# Temp_Bank.net
KiCad netlist of a schematic drawn in Altium Designer
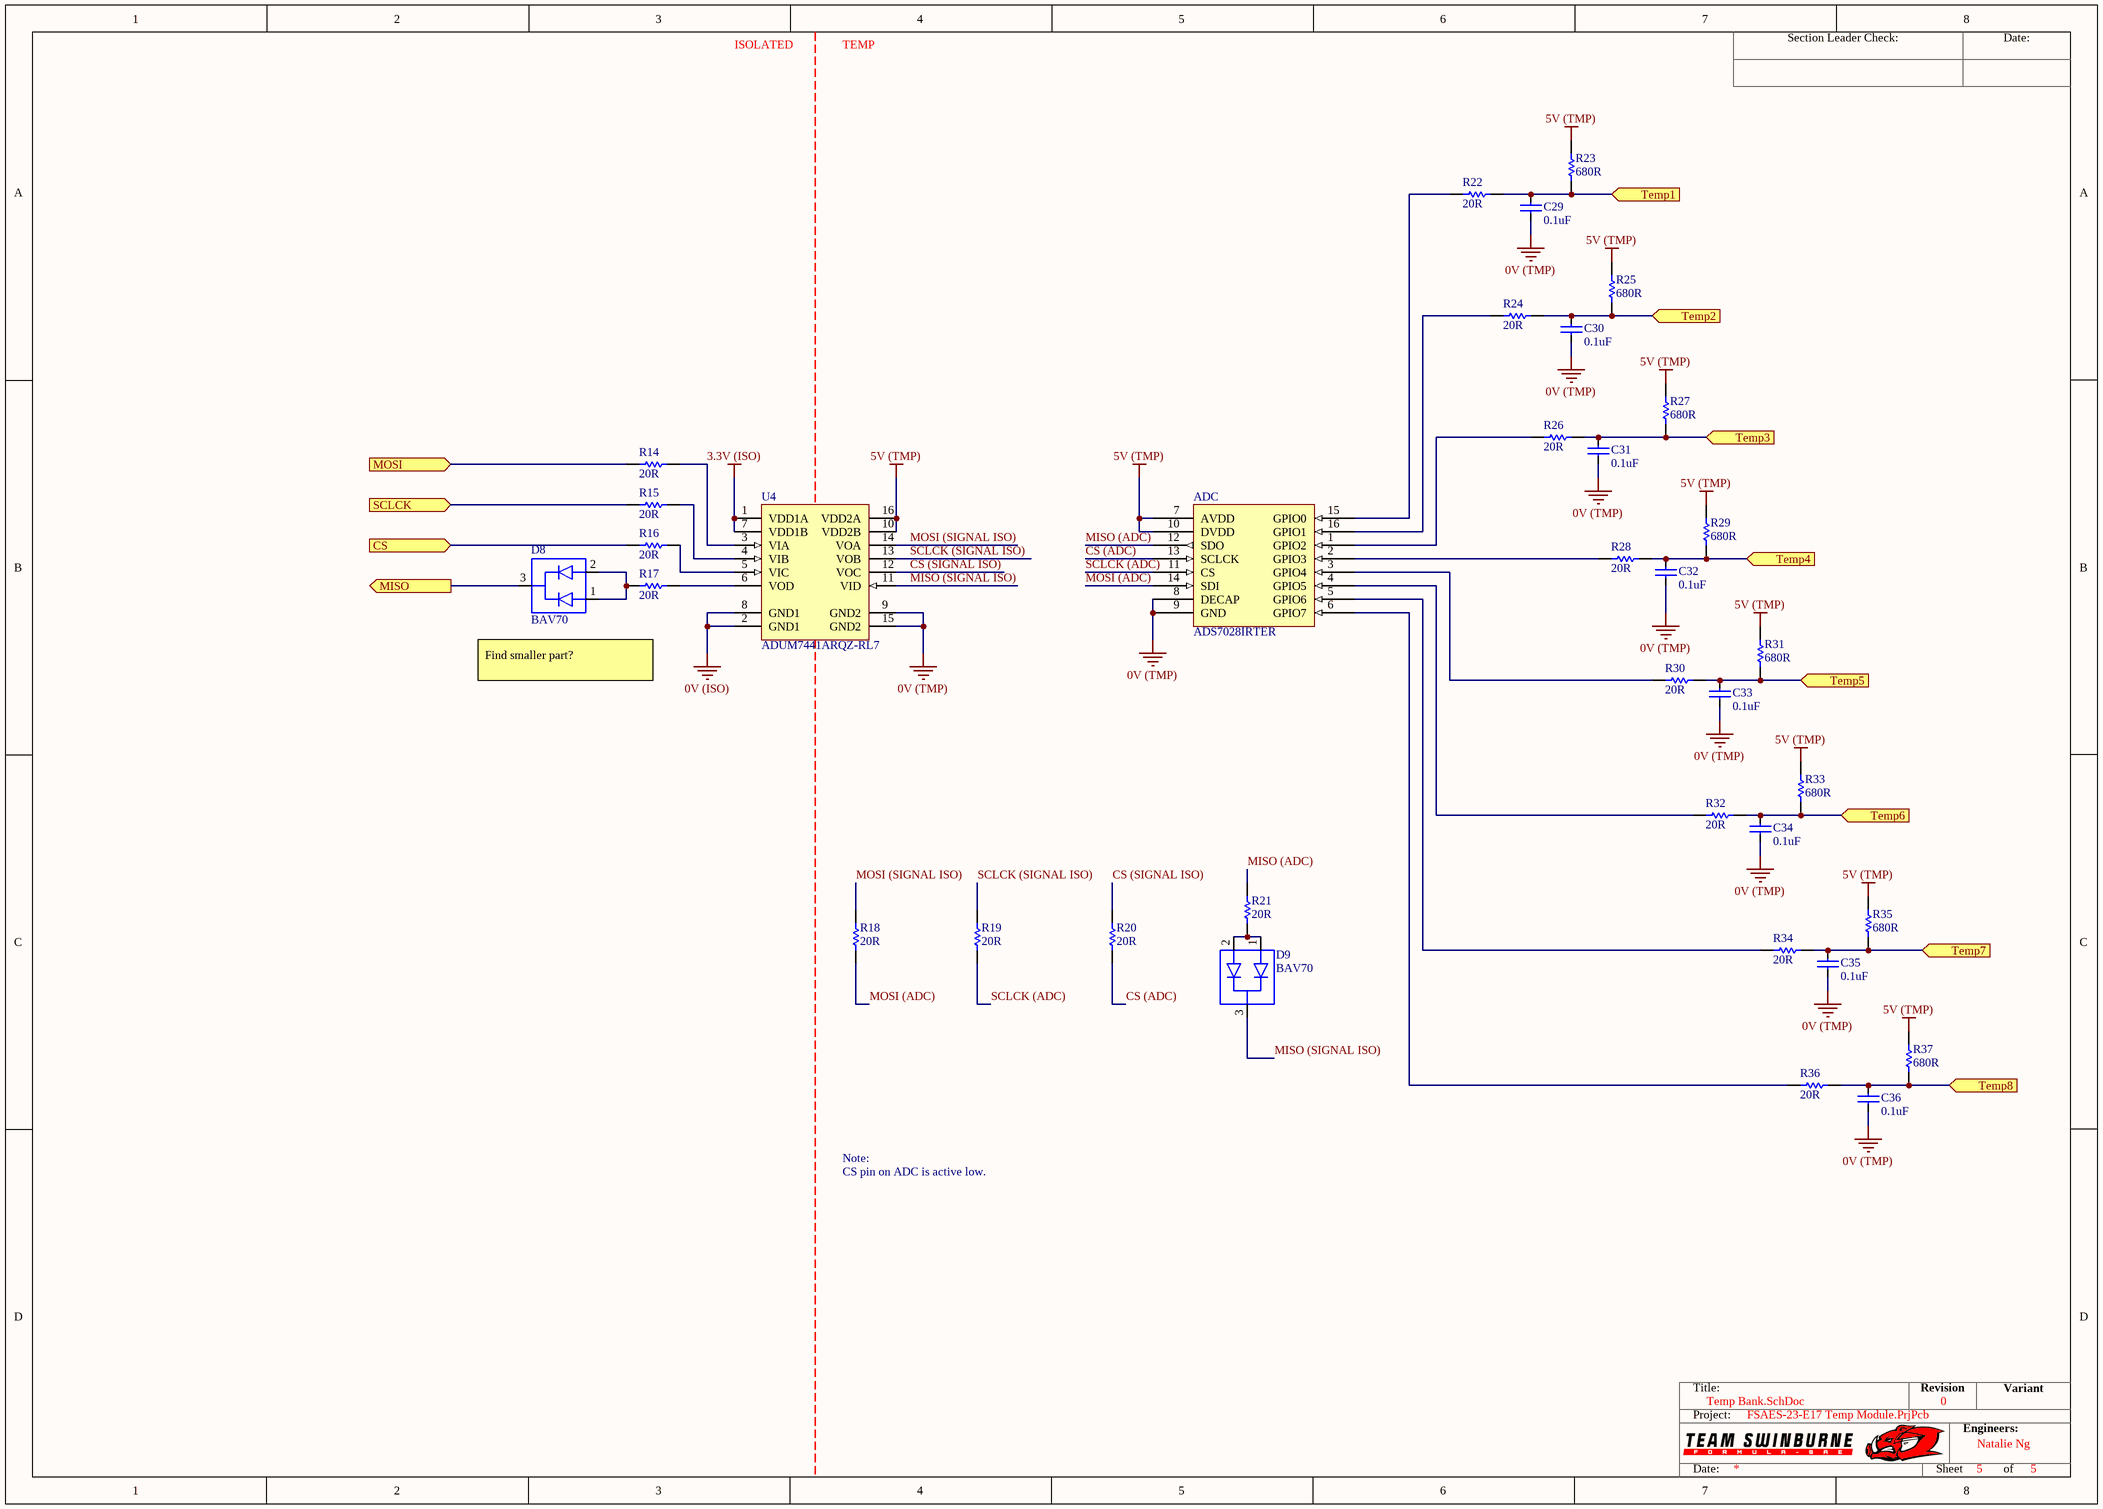
[diagram p0: Temp Bank.SchDoc]

(export (version "E")
  (design (tool "Eeschema 10.0.6"))
  (components
    (comp (ref "ADC")
      (value "ADS7028IRTER")
      (footprint "QFN50P300X300X80_HS-17N")
      (description "Small 8-channel 12-bit analog-to-digital converter (ADC) with SPI, GPIOs and CRC 16-WQFN -40 to 85")
      (libsource (lib "Team Swinburne") (part "ADS7028IRTER-Symbol-1"))
    )
    (comp (ref "C29")
      (value "0.1uF")
      (footprint "0805")
      (description "Cap Ceramic 0.1uF 25V X7R 10% Pad SMD 0805 125C Automotive T/R")
      (fields (field (name "TOLERANCE") "10%"))
      (libsource (lib "Team Swinburne") (part "Capacitors"))
    )
    (comp (ref "C30")
      (value "0.1uF")
      (footprint "0805")
      (description "Cap Ceramic 0.1uF 25V X7R 10% Pad SMD 0805 125C Automotive T/R")
      (fields (field (name "TOLERANCE") "10%"))
      (libsource (lib "Team Swinburne") (part "Capacitors"))
    )
    (comp (ref "C31")
      (value "0.1uF")
      (footprint "0805")
      (description "Cap Ceramic 0.1uF 25V X7R 10% Pad SMD 0805 125C Automotive T/R")
      (fields (field (name "TOLERANCE") "10%"))
      (libsource (lib "Team Swinburne") (part "Capacitors"))
    )
    (comp (ref "C32")
      (value "0.1uF")
      (footprint "0805")
      (description "Cap Ceramic 0.1uF 25V X7R 10% Pad SMD 0805 125C Automotive T/R")
      (fields (field (name "TOLERANCE") "10%"))
      (libsource (lib "Team Swinburne") (part "Capacitors"))
    )
    (comp (ref "C33")
      (value "0.1uF")
      (footprint "0805")
      (description "Cap Ceramic 0.1uF 25V X7R 10% Pad SMD 0805 125C Automotive T/R")
      (fields (field (name "TOLERANCE") "10%"))
      (libsource (lib "Team Swinburne") (part "Capacitors"))
    )
    (comp (ref "C34")
      (value "0.1uF")
      (footprint "0805")
      (description "Cap Ceramic 0.1uF 25V X7R 10% Pad SMD 0805 125C Automotive T/R")
      (fields (field (name "TOLERANCE") "10%"))
      (libsource (lib "Team Swinburne") (part "Capacitors"))
    )
    (comp (ref "C35")
      (value "0.1uF")
      (footprint "0805")
      (description "Cap Ceramic 0.1uF 25V X7R 10% Pad SMD 0805 125C Automotive T/R")
      (fields (field (name "TOLERANCE") "10%"))
      (libsource (lib "Team Swinburne") (part "Capacitors"))
    )
    (comp (ref "C36")
      (value "0.1uF")
      (footprint "0805")
      (description "Cap Ceramic 0.1uF 25V X7R 10% Pad SMD 0805 125C Automotive T/R")
      (fields (field (name "TOLERANCE") "10%"))
      (libsource (lib "Team Swinburne") (part "Capacitors"))
    )
    (comp (ref "D8")
      (value "BAV70")
      (footprint "BAV70-Footprint-1")
      (description "DIODE ARRAY GP 70V 200mA SOT23-3")
      (libsource (lib "Team Swinburne") (part "BAV70-Symbol-1"))
    )
    (comp (ref "D9")
      (value "BAV70")
      (footprint "BAV70-Footprint-1")
      (description "DIODE ARRAY GP 70V 200mA SOT23-3")
      (libsource (lib "Team Swinburne") (part "BAV70-Symbol-1"))
    )
    (comp (ref "R14")
      (value "20R")
      (footprint "RESC0603")
      (description "RES SMD 20 OHM JUMPER 1/10W 0603")
      (fields (field (name "TOLERANCE") "1%"))
      (libsource (lib "Team Swinburne") (part "Resistor"))
    )
    (comp (ref "R15")
      (value "20R")
      (footprint "RESC0603")
      (description "RES SMD 20 OHM JUMPER 1/10W 0603")
      (fields (field (name "TOLERANCE") "1%"))
      (libsource (lib "Team Swinburne") (part "Resistor"))
    )
    (comp (ref "R16")
      (value "20R")
      (footprint "RESC0603")
      (description "RES SMD 20 OHM JUMPER 1/10W 0603")
      (fields (field (name "TOLERANCE") "1%"))
      (libsource (lib "Team Swinburne") (part "Resistor"))
    )
    (comp (ref "R17")
      (value "20R")
      (footprint "RESC0603")
      (description "RES SMD 20 OHM JUMPER 1/10W 0603")
      (fields (field (name "TOLERANCE") "1%"))
      (libsource (lib "Team Swinburne") (part "Resistor"))
    )
    (comp (ref "R18")
      (value "20R")
      (footprint "RESC0603")
      (description "RES SMD 20 OHM JUMPER 1/10W 0603")
      (fields (field (name "TOLERANCE") "1%"))
      (libsource (lib "Team Swinburne") (part "Resistor"))
    )
    (comp (ref "R19")
      (value "20R")
      (footprint "RESC0603")
      (description "RES SMD 20 OHM JUMPER 1/10W 0603")
      (fields (field (name "TOLERANCE") "1%"))
      (libsource (lib "Team Swinburne") (part "Resistor"))
    )
    (comp (ref "R20")
      (value "20R")
      (footprint "RESC0603")
      (description "RES SMD 20 OHM JUMPER 1/10W 0603")
      (fields (field (name "TOLERANCE") "1%"))
      (libsource (lib "Team Swinburne") (part "Resistor"))
    )
    (comp (ref "R21")
      (value "20R")
      (footprint "RESC0603")
      (description "RES SMD 20 OHM JUMPER 1/10W 0603")
      (fields (field (name "TOLERANCE") "1%"))
      (libsource (lib "Team Swinburne") (part "Resistor"))
    )
    (comp (ref "R22")
      (value "20R")
      (footprint "RESC0603")
      (description "RES SMD 20 OHM JUMPER 1/10W 0603")
      (fields (field (name "TOLERANCE") "1%"))
      (libsource (lib "Team Swinburne") (part "Resistor"))
    )
    (comp (ref "R23")
      (value "680R")
      (footprint "0805")
      (description "RC0805FR07680RL")
      (fields (field (name "DIGIKEY PART NUMBER") "311-680CRCT-ND") (field (name "TOLERANCE") "0.01"))
      (libsource (lib "Team Swinburne") (part "Resistor"))
    )
    (comp (ref "R24")
      (value "20R")
      (footprint "RESC0603")
      (description "RES SMD 20 OHM JUMPER 1/10W 0603")
      (fields (field (name "TOLERANCE") "1%"))
      (libsource (lib "Team Swinburne") (part "Resistor"))
    )
    (comp (ref "R25")
      (value "680R")
      (footprint "0805")
      (description "RC0805FR07680RL")
      (fields (field (name "DIGIKEY PART NUMBER") "311-680CRCT-ND") (field (name "TOLERANCE") "0.01"))
      (libsource (lib "Team Swinburne") (part "Resistor"))
    )
    (comp (ref "R26")
      (value "20R")
      (footprint "RESC0603")
      (description "RES SMD 20 OHM JUMPER 1/10W 0603")
      (fields (field (name "TOLERANCE") "1%"))
      (libsource (lib "Team Swinburne") (part "Resistor"))
    )
    (comp (ref "R27")
      (value "680R")
      (footprint "0805")
      (description "RC0805FR07680RL")
      (fields (field (name "DIGIKEY PART NUMBER") "311-680CRCT-ND") (field (name "TOLERANCE") "0.01"))
      (libsource (lib "Team Swinburne") (part "Resistor"))
    )
    (comp (ref "R28")
      (value "20R")
      (footprint "RESC0603")
      (description "RES SMD 20 OHM JUMPER 1/10W 0603")
      (fields (field (name "TOLERANCE") "1%"))
      (libsource (lib "Team Swinburne") (part "Resistor"))
    )
    (comp (ref "R29")
      (value "680R")
      (footprint "0805")
      (description "RC0805FR07680RL")
      (fields (field (name "DIGIKEY PART NUMBER") "311-680CRCT-ND") (field (name "TOLERANCE") "0.01"))
      (libsource (lib "Team Swinburne") (part "Resistor"))
    )
    (comp (ref "R30")
      (value "20R")
      (footprint "RESC0603")
      (description "RES SMD 20 OHM JUMPER 1/10W 0603")
      (fields (field (name "TOLERANCE") "1%"))
      (libsource (lib "Team Swinburne") (part "Resistor"))
    )
    (comp (ref "R31")
      (value "680R")
      (footprint "0805")
      (description "RC0805FR07680RL")
      (fields (field (name "DIGIKEY PART NUMBER") "311-680CRCT-ND") (field (name "TOLERANCE") "0.01"))
      (libsource (lib "Team Swinburne") (part "Resistor"))
    )
    (comp (ref "R32")
      (value "20R")
      (footprint "RESC0603")
      (description "RES SMD 20 OHM JUMPER 1/10W 0603")
      (fields (field (name "TOLERANCE") "1%"))
      (libsource (lib "Team Swinburne") (part "Resistor"))
    )
    (comp (ref "R33")
      (value "680R")
      (footprint "0805")
      (description "RC0805FR07680RL")
      (fields (field (name "DIGIKEY PART NUMBER") "311-680CRCT-ND") (field (name "TOLERANCE") "0.01"))
      (libsource (lib "Team Swinburne") (part "Resistor"))
    )
    (comp (ref "R34")
      (value "20R")
      (footprint "RESC0603")
      (description "RES SMD 20 OHM JUMPER 1/10W 0603")
      (fields (field (name "TOLERANCE") "1%"))
      (libsource (lib "Team Swinburne") (part "Resistor"))
    )
    (comp (ref "R35")
      (value "680R")
      (footprint "0805")
      (description "RC0805FR07680RL")
      (fields (field (name "DIGIKEY PART NUMBER") "311-680CRCT-ND") (field (name "TOLERANCE") "0.01"))
      (libsource (lib "Team Swinburne") (part "Resistor"))
    )
    (comp (ref "R36")
      (value "20R")
      (footprint "RESC0603")
      (description "RES SMD 20 OHM JUMPER 1/10W 0603")
      (fields (field (name "TOLERANCE") "1%"))
      (libsource (lib "Team Swinburne") (part "Resistor"))
    )
    (comp (ref "R37")
      (value "680R")
      (footprint "0805")
      (description "RC0805FR07680RL")
      (fields (field (name "DIGIKEY PART NUMBER") "311-680CRCT-ND") (field (name "TOLERANCE") "0.01"))
      (libsource (lib "Team Swinburne") (part "Resistor"))
    )
    (comp (ref "U4")
      (value "ADUM7441ARQZ-RL7")
      (footprint "ADI-RQ-16_M")
      (description "Digital Isolator CMOS 4-CH 1Mbps 16-Pin QSOP T/R")
      (libsource (lib "Team Swinburne") (part "ADI-ADUM7441-RQ-16"))
    )
  )
  (nets
    (net (code "1") (name "/CS") (class "Default")
      (node (ref "R16") (pin "1") (pinfunction "1_1") (pintype "passive"))
    )
    (net (code "2") (name "/CS (ADC)") (class "Default")
      (node (ref "ADC") (pin "13") (pinfunction "SCLCK_13") (pintype "input"))
      (node (ref "R20") (pin "1") (pinfunction "1_1") (pintype "passive"))
    )
    (net (code "3") (name "/CS (SIGNAL ISO)") (class "Default")
      (node (ref "R20") (pin "2") (pinfunction "2_2") (pintype "passive"))
      (node (ref "U4") (pin "12") (pinfunction "VOC_12") (pintype "tri_state"))
    )
    (net (code "4") (name "/MISO") (class "Default")
      (node (ref "D8") (pin "3") (pinfunction "CC_3") (pintype "passive"))
    )
    (net (code "5") (name "/MISO (ADC)") (class "Default")
      (node (ref "ADC") (pin "12") (pinfunction "SDO_12") (pintype "output"))
      (node (ref "R21") (pin "2") (pinfunction "2_2") (pintype "passive"))
    )
    (net (code "6") (name "/MISO (SIGNAL ISO)") (class "Default")
      (node (ref "D9") (pin "3") (pinfunction "CC_3") (pintype "passive"))
      (node (ref "U4") (pin "11") (pinfunction "VID_11") (pintype "input"))
    )
    (net (code "7") (name "/MOSI") (class "Default")
      (node (ref "R14") (pin "1") (pinfunction "1_1") (pintype "passive"))
    )
    (net (code "8") (name "/MOSI (ADC)") (class "Default")
      (node (ref "ADC") (pin "14") (pinfunction "SDI_14") (pintype "input"))
      (node (ref "R18") (pin "1") (pinfunction "1_1") (pintype "passive"))
    )
    (net (code "9") (name "/MOSI (SIGNAL ISO)") (class "Default")
      (node (ref "R18") (pin "2") (pinfunction "2_2") (pintype "passive"))
      (node (ref "U4") (pin "14") (pinfunction "VOA_14") (pintype "tri_state"))
    )
    (net (code "10") (name "/SCLCK") (class "Default")
      (node (ref "R15") (pin "1") (pinfunction "1_1") (pintype "passive"))
    )
    (net (code "11") (name "/SCLCK (ADC)") (class "Default")
      (node (ref "ADC") (pin "11") (pinfunction "CS_11") (pintype "input"))
      (node (ref "R19") (pin "1") (pinfunction "1_1") (pintype "passive"))
    )
    (net (code "12") (name "/SCLCK (SIGNAL ISO)") (class "Default")
      (node (ref "R19") (pin "2") (pinfunction "2_2") (pintype "passive"))
      (node (ref "U4") (pin "13") (pinfunction "VOB_13") (pintype "tri_state"))
    )
    (net (code "13") (name "/Temp1") (class "Default")
      (node (ref "C29") (pin "1") (pinfunction "1_1") (pintype "passive"))
      (node (ref "R22") (pin "2") (pinfunction "2_2") (pintype "passive"))
      (node (ref "R23") (pin "1") (pinfunction "1_1") (pintype "passive"))
    )
    (net (code "14") (name "/Temp2") (class "Default")
      (node (ref "C30") (pin "1") (pinfunction "1_1") (pintype "passive"))
      (node (ref "R24") (pin "2") (pinfunction "2_2") (pintype "passive"))
      (node (ref "R25") (pin "1") (pinfunction "1_1") (pintype "passive"))
    )
    (net (code "15") (name "/Temp3") (class "Default")
      (node (ref "C31") (pin "1") (pinfunction "1_1") (pintype "passive"))
      (node (ref "R26") (pin "2") (pinfunction "2_2") (pintype "passive"))
      (node (ref "R27") (pin "1") (pinfunction "1_1") (pintype "passive"))
    )
    (net (code "16") (name "/Temp4") (class "Default")
      (node (ref "C32") (pin "1") (pinfunction "1_1") (pintype "passive"))
      (node (ref "R28") (pin "2") (pinfunction "2_2") (pintype "passive"))
      (node (ref "R29") (pin "1") (pinfunction "1_1") (pintype "passive"))
    )
    (net (code "17") (name "/Temp5") (class "Default")
      (node (ref "C33") (pin "1") (pinfunction "1_1") (pintype "passive"))
      (node (ref "R30") (pin "2") (pinfunction "2_2") (pintype "passive"))
      (node (ref "R31") (pin "1") (pinfunction "1_1") (pintype "passive"))
    )
    (net (code "18") (name "/Temp6") (class "Default")
      (node (ref "C34") (pin "1") (pinfunction "1_1") (pintype "passive"))
      (node (ref "R32") (pin "2") (pinfunction "2_2") (pintype "passive"))
      (node (ref "R33") (pin "1") (pinfunction "1_1") (pintype "passive"))
    )
    (net (code "19") (name "/Temp7") (class "Default")
      (node (ref "C35") (pin "1") (pinfunction "1_1") (pintype "passive"))
      (node (ref "R34") (pin "2") (pinfunction "2_2") (pintype "passive"))
      (node (ref "R35") (pin "1") (pinfunction "1_1") (pintype "passive"))
    )
    (net (code "20") (name "/Temp8") (class "Default")
      (node (ref "C36") (pin "1") (pinfunction "1_1") (pintype "passive"))
      (node (ref "R36") (pin "2") (pinfunction "2_2") (pintype "passive"))
      (node (ref "R37") (pin "1") (pinfunction "1_1") (pintype "passive"))
    )
    (net (code "21") (name "0V (ISO)") (class "Default")
      (node (ref "U4") (pin "2") (pinfunction "GND1_2") (pintype "power_in"))
      (node (ref "U4") (pin "8") (pinfunction "GND1_8") (pintype "power_in"))
    )
    (net (code "22") (name "0V (TMP)") (class "Default")
      (node (ref "ADC") (pin "8") (pinfunction "DECAP_8") (pintype "power_in"))
      (node (ref "ADC") (pin "9") (pinfunction "GND_9") (pintype "power_in"))
      (node (ref "C29") (pin "2") (pinfunction "2_2") (pintype "passive"))
      (node (ref "C30") (pin "2") (pinfunction "2_2") (pintype "passive"))
      (node (ref "C31") (pin "2") (pinfunction "2_2") (pintype "passive"))
      (node (ref "C32") (pin "2") (pinfunction "2_2") (pintype "passive"))
      (node (ref "C33") (pin "2") (pinfunction "2_2") (pintype "passive"))
      (node (ref "C34") (pin "2") (pinfunction "2_2") (pintype "passive"))
      (node (ref "C35") (pin "2") (pinfunction "2_2") (pintype "passive"))
      (node (ref "C36") (pin "2") (pinfunction "2_2") (pintype "passive"))
      (node (ref "U4") (pin "15") (pinfunction "GND2_15") (pintype "power_in"))
      (node (ref "U4") (pin "9") (pinfunction "GND2_9") (pintype "power_in"))
    )
    (net (code "23") (name "3.3V (ISO)") (class "Default")
      (node (ref "U4") (pin "1") (pinfunction "VDD1A_1") (pintype "power_in"))
      (node (ref "U4") (pin "7") (pinfunction "VDD1B_7") (pintype "power_in"))
    )
    (net (code "24") (name "5V (TMP)") (class "Default")
      (node (ref "ADC") (pin "10") (pinfunction "DVDD_10") (pintype "power_in"))
      (node (ref "ADC") (pin "7") (pinfunction "AVDD_7") (pintype "power_in"))
      (node (ref "R23") (pin "2") (pinfunction "2_2") (pintype "passive"))
      (node (ref "R25") (pin "2") (pinfunction "2_2") (pintype "passive"))
      (node (ref "R27") (pin "2") (pinfunction "2_2") (pintype "passive"))
      (node (ref "R29") (pin "2") (pinfunction "2_2") (pintype "passive"))
      (node (ref "R31") (pin "2") (pinfunction "2_2") (pintype "passive"))
      (node (ref "R33") (pin "2") (pinfunction "2_2") (pintype "passive"))
      (node (ref "R35") (pin "2") (pinfunction "2_2") (pintype "passive"))
      (node (ref "R37") (pin "2") (pinfunction "2_2") (pintype "passive"))
      (node (ref "U4") (pin "10") (pinfunction "VDD2B_10") (pintype "power_in"))
      (node (ref "U4") (pin "16") (pinfunction "VDD2A_16") (pintype "power_in"))
    )
    (net (code "25") (name "Net-(ADC-GPIO0)") (class "Default")
      (node (ref "ADC") (pin "15") (pinfunction "GPIO0_15") (pintype "input"))
      (node (ref "R22") (pin "1") (pinfunction "1_1") (pintype "passive"))
    )
    (net (code "26") (name "Net-(ADC-GPIO1)") (class "Default")
      (node (ref "ADC") (pin "16") (pinfunction "GPIO1_16") (pintype "input"))
      (node (ref "R24") (pin "1") (pinfunction "1_1") (pintype "passive"))
    )
    (net (code "27") (name "Net-(ADC-GPIO2)") (class "Default")
      (node (ref "ADC") (pin "1") (pinfunction "GPIO2_1") (pintype "input"))
      (node (ref "R26") (pin "1") (pinfunction "1_1") (pintype "passive"))
    )
    (net (code "28") (name "Net-(ADC-GPIO3)") (class "Default")
      (node (ref "ADC") (pin "2") (pinfunction "GPIO3_2") (pintype "input"))
      (node (ref "R28") (pin "1") (pinfunction "1_1") (pintype "passive"))
    )
    (net (code "29") (name "Net-(ADC-GPIO4)") (class "Default")
      (node (ref "ADC") (pin "3") (pinfunction "GPIO4_3") (pintype "input"))
      (node (ref "R30") (pin "1") (pinfunction "1_1") (pintype "passive"))
    )
    (net (code "30") (name "Net-(ADC-GPIO5)") (class "Default")
      (node (ref "ADC") (pin "4") (pinfunction "GPIO5_4") (pintype "input"))
      (node (ref "R32") (pin "1") (pinfunction "1_1") (pintype "passive"))
    )
    (net (code "31") (name "Net-(ADC-GPIO6)") (class "Default")
      (node (ref "ADC") (pin "5") (pinfunction "GPIO6_5") (pintype "input"))
      (node (ref "R34") (pin "1") (pinfunction "1_1") (pintype "passive"))
    )
    (net (code "32") (name "Net-(ADC-GPIO7)") (class "Default")
      (node (ref "ADC") (pin "6") (pinfunction "GPIO7_6") (pintype "input"))
      (node (ref "R36") (pin "1") (pinfunction "1_1") (pintype "passive"))
    )
    (net (code "33") (name "Net-(D8-A1)") (class "Default")
      (node (ref "D8") (pin "1") (pinfunction "A1_1") (pintype "passive"))
      (node (ref "D8") (pin "2") (pinfunction "A2_2") (pintype "passive"))
      (node (ref "R17") (pin "1") (pinfunction "1_1") (pintype "passive"))
    )
    (net (code "34") (name "Net-(D9-A1)") (class "Default")
      (node (ref "D9") (pin "1") (pinfunction "A1_1") (pintype "passive"))
      (node (ref "D9") (pin "2") (pinfunction "A2_2") (pintype "passive"))
      (node (ref "R21") (pin "1") (pinfunction "1_1") (pintype "passive"))
    )
    (net (code "35") (name "Net-(U4-VIA)") (class "Default")
      (node (ref "R14") (pin "2") (pinfunction "2_2") (pintype "passive"))
      (node (ref "U4") (pin "3") (pinfunction "VIA_3") (pintype "input"))
    )
    (net (code "36") (name "Net-(U4-VIB)") (class "Default")
      (node (ref "R15") (pin "2") (pinfunction "2_2") (pintype "passive"))
      (node (ref "U4") (pin "4") (pinfunction "VIB_4") (pintype "input"))
    )
    (net (code "37") (name "Net-(U4-VIC)") (class "Default")
      (node (ref "R16") (pin "2") (pinfunction "2_2") (pintype "passive"))
      (node (ref "U4") (pin "5") (pinfunction "VIC_5") (pintype "input"))
    )
    (net (code "38") (name "Net-(U4-VOD)") (class "Default")
      (node (ref "R17") (pin "2") (pinfunction "2_2") (pintype "passive"))
      (node (ref "U4") (pin "6") (pinfunction "VOD_6") (pintype "tri_state"))
    )
  )
)
